# gps.net
KiCad netlist of a schematic drawn in Altium Designer
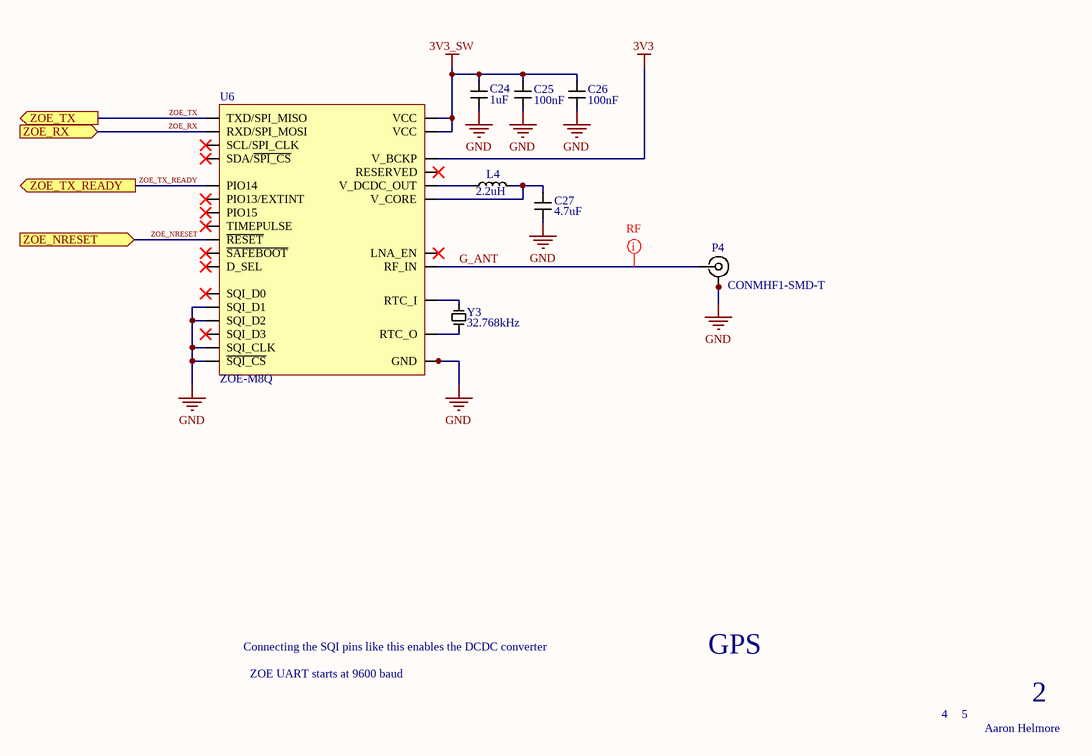
[diagram p0: gps.SchDoc]

(export (version "E")
  (design (tool "Eeschema 10.0.6"))
  (components
    (comp (ref "C24")
      (value "1uF")
      (footprint "CAP_0402")
      (fields (field (name "VOLTAGE") "25V"))
      (libsource (lib "thesis_schem_lib") (part "Capacitor"))
    )
    (comp (ref "C25")
      (value "100nF")
      (footprint "CAP_0402")
      (fields (field (name "VOLTAGE") "25V"))
      (libsource (lib "thesis_schem_lib") (part "Capacitor"))
    )
    (comp (ref "C26")
      (value "100nF")
      (footprint "CAP_0402")
      (fields (field (name "VOLTAGE") "25V"))
      (libsource (lib "thesis_schem_lib") (part "Capacitor"))
    )
    (comp (ref "C27")
      (value "4.7uF")
      (footprint "CAP_0603")
      (fields (field (name "VOLTAGE") "6.3V"))
      (libsource (lib "thesis_schem_lib") (part "Capacitor"))
    )
    (comp (ref "L4")
      (value "2.2uH")
      (footprint "LQM2MPNxxxx")
      (libsource (lib "thesis_schem_lib") (part "Inductor"))
    )
    (comp (ref "P4")
      (value "CONMHF1-SMD-T")
      (footprint "CONMHF1-SMD-T")
      (libsource (lib "thesis_schem_lib") (part "CONMHF1-SMD-T"))
    )
    (comp (ref "U6")
      (value "ZOE-M8Q")
      (footprint "ZOE-M8Q")
      (description "ublox GPS/GNSS receiver")
      (libsource (lib "thesis_schem_lib") (part "ZOE-M8Q"))
    )
    (comp (ref "Y3")
      (value "32.768kHz")
      (footprint "2-SMD")
      (libsource (lib "thesis_schem_lib") (part "Crystal_2_1"))
    )
  )
  (nets
    (net (code "1") (name "/G_ANT") (class "Default")
      (node (ref "P4") (pin "1") (pinfunction "VCC_1") (pintype "passive"))
      (node (ref "U6") (pin "A4") (pinfunction "RF_IN_A4") (pintype "passive"))
    )
    (net (code "2") (name "/ZOE_NRESET") (class "Default")
      (node (ref "U6") (pin "J6") (pinfunction "~{RESET}_J6") (pintype "passive"))
    )
    (net (code "3") (name "/ZOE_RX") (class "Default")
      (node (ref "U6") (pin "J4") (pinfunction "RXD/SPI_MOSI_J4") (pintype "passive"))
    )
    (net (code "4") (name "/ZOE_TX") (class "Default")
      (node (ref "U6") (pin "J5") (pinfunction "TXD/SPI_MISO_J5") (pintype "passive"))
    )
    (net (code "5") (name "/ZOE_TX_READY") (class "Default")
      (node (ref "U6") (pin "F6") (pinfunction "PIO14_F6") (pintype "passive"))
    )
    (net (code "6") (name "3V3") (class "Default")
      (node (ref "U6") (pin "H9") (pinfunction "V_BCKP_H9") (pintype "passive"))
    )
    (net (code "7") (name "3V3_SW") (class "Default")
      (node (ref "C24") (pin "2") (pinfunction "J11_2") (pintype "passive"))
      (node (ref "C25") (pin "2") (pinfunction "J11_2") (pintype "passive"))
      (node (ref "C26") (pin "2") (pinfunction "J11_2") (pintype "passive"))
      (node (ref "U6") (pin "J1") (pinfunction "VCC_J1") (pintype "passive"))
      (node (ref "U6") (pin "J2") (pinfunction "VCC_J2") (pintype "passive"))
    )
    (net (code "8") (name "GND") (class "Default")
      (node (ref "C24") (pin "1") (pinfunction "J12_1") (pintype "passive"))
      (node (ref "C25") (pin "1") (pinfunction "J12_1") (pintype "passive"))
      (node (ref "C26") (pin "1") (pinfunction "J12_1") (pintype "passive"))
      (node (ref "C27") (pin "1") (pinfunction "J12_1") (pintype "passive"))
      (node (ref "P4") (pin "2") (pinfunction "VCC_2") (pintype "passive"))
      (node (ref "P4") (pin "3") (pinfunction "VCC_3") (pintype "passive"))
      (node (ref "P4") (pin "4") (pinfunction "VCC_4") (pintype "passive"))
      (node (ref "U6") (pin "A1") (pinfunction "GND_A1") (pintype "passive"))
      (node (ref "U6") (pin "A3") (pinfunction "GND_A3") (pintype "passive"))
      (node (ref "U6") (pin "A5") (pinfunction "GND_A5") (pintype "passive"))
      (node (ref "U6") (pin "A7") (pinfunction "GND_A7") (pintype "passive"))
      (node (ref "U6") (pin "A8") (pinfunction "GND_A8") (pintype "passive"))
      (node (ref "U6") (pin "A9") (pinfunction "GND_A9") (pintype "passive"))
      (node (ref "U6") (pin "B9") (pinfunction "GND_B9") (pintype "passive"))
      (node (ref "U6") (pin "C1") (pinfunction "SQI_D1_C1") (pintype "passive"))
      (node (ref "U6") (pin "C7") (pinfunction "GND_C7") (pintype "passive"))
      (node (ref "U6") (pin "C9") (pinfunction "GND_C9") (pintype "passive"))
      (node (ref "U6") (pin "D3") (pinfunction "~{SQI_CS}_D3") (pintype "passive"))
      (node (ref "U6") (pin "D6") (pinfunction "GND_D6") (pintype "passive"))
      (node (ref "U6") (pin "D9") (pinfunction "GND_D9") (pintype "passive"))
      (node (ref "U6") (pin "E1") (pinfunction "SQI_CLK_E1") (pintype "passive"))
      (node (ref "U6") (pin "E3") (pinfunction "SQI_D2_E3") (pintype "passive"))
      (node (ref "U6") (pin "E7") (pinfunction "GND_E7") (pintype "passive"))
      (node (ref "U6") (pin "F7") (pinfunction "GND_F7") (pintype "passive"))
      (node (ref "U6") (pin "G3") (pinfunction "GND_G3") (pintype "passive"))
      (node (ref "U6") (pin "G6") (pinfunction "GND_G6") (pintype "passive"))
      (node (ref "U6") (pin "G7") (pinfunction "GND_G7") (pintype "passive"))
      (node (ref "U6") (pin "J3") (pinfunction "GND_J3") (pintype "passive"))
      (node (ref "U6") (pin "J9") (pinfunction "GND_J9") (pintype "passive"))
    )
    (net (code "9") (name "Net-(C27-J11)") (class "Default")
      (node (ref "C27") (pin "2") (pinfunction "J11_2") (pintype "passive"))
      (node (ref "L4") (pin "2") (pinfunction "2_2") (pintype "passive"))
      (node (ref "U6") (pin "G1") (pinfunction "V_CORE_G1") (pintype "passive"))
    )
    (net (code "10") (name "Net-(U6-RTC_I)") (class "Default")
      (node (ref "U6") (pin "J7") (pinfunction "RTC_I_J7") (pintype "passive"))
      (node (ref "Y3") (pin "2") (pinfunction "2_2") (pintype "passive"))
    )
    (net (code "11") (name "Net-(U6-RTC_O)") (class "Default")
      (node (ref "U6") (pin "J8") (pinfunction "RTC_O_J8") (pintype "passive"))
      (node (ref "Y3") (pin "1") (pinfunction "1_1") (pintype "passive"))
    )
    (net (code "12") (name "Net-(U6-V_DCDC_OUT)") (class "Default")
      (node (ref "L4") (pin "1") (pinfunction "1_1") (pintype "passive"))
      (node (ref "U6") (pin "H1") (pinfunction "V_DCDC_OUT_H1") (pintype "passive"))
    )
    (net (code "13") (name "unconnected-(U6-D_SEL-PadD4)") (class "Default")
      (node (ref "U6") (pin "D4") (pinfunction "D_SEL_D4") (pintype "passive+no_connect"))
    )
    (net (code "14") (name "unconnected-(U6-LNA_EN-PadC5)") (class "Default")
      (node (ref "U6") (pin "C5") (pinfunction "LNA_EN_C5") (pintype "passive+no_connect"))
    )
    (net (code "15") (name "unconnected-(U6-PIO13{slash}EXTINT-PadG4)") (class "Default")
      (node (ref "U6") (pin "G4") (pinfunction "PIO13/EXTINT_G4") (pintype "passive+no_connect"))
    )
    (net (code "16") (name "unconnected-(U6-PIO15-PadC6)") (class "Default")
      (node (ref "U6") (pin "C6") (pinfunction "PIO15_C6") (pintype "passive+no_connect"))
    )
    (net (code "17") (name "unconnected-(U6-RESERVED-PadG9)") (class "Default")
      (node (ref "U6") (pin "G9") (pinfunction "RESERVED_G9") (pintype "passive+no_connect"))
    )
    (net (code "18") (name "unconnected-(U6-SCL{slash}SPI_CLK-PadB1)") (class "Default")
      (node (ref "U6") (pin "B1") (pinfunction "SCL/SPI_CLK_B1") (pintype "passive+no_connect"))
    )
    (net (code "19") (name "unconnected-(U6-SDA{slash}~{SPI_CS}-PadA2)") (class "Default")
      (node (ref "U6") (pin "A2") (pinfunction "SDA/~{SPI_CS}_A2") (pintype "passive+no_connect"))
    )
    (net (code "20") (name "unconnected-(U6-SQI_D0-PadD1)") (class "Default")
      (node (ref "U6") (pin "D1") (pinfunction "SQI_D0_D1") (pintype "passive+no_connect"))
    )
    (net (code "21") (name "unconnected-(U6-SQI_D3-PadF3)") (class "Default")
      (node (ref "U6") (pin "F3") (pinfunction "SQI_D3_F3") (pintype "passive+no_connect"))
    )
    (net (code "22") (name "unconnected-(U6-TIMEPULSE-PadC3)") (class "Default")
      (node (ref "U6") (pin "C3") (pinfunction "TIMEPULSE_C3") (pintype "passive+no_connect"))
    )
    (net (code "23") (name "unconnected-(U6-~{SAFEBOOT}-PadC4)") (class "Default")
      (node (ref "U6") (pin "C4") (pinfunction "~{SAFEBOOT}_C4") (pintype "passive+no_connect"))
    )
  )
)
